# rhythkey_V1.net
KiCad netlist of a schematic drawn in EasyEDA Pro
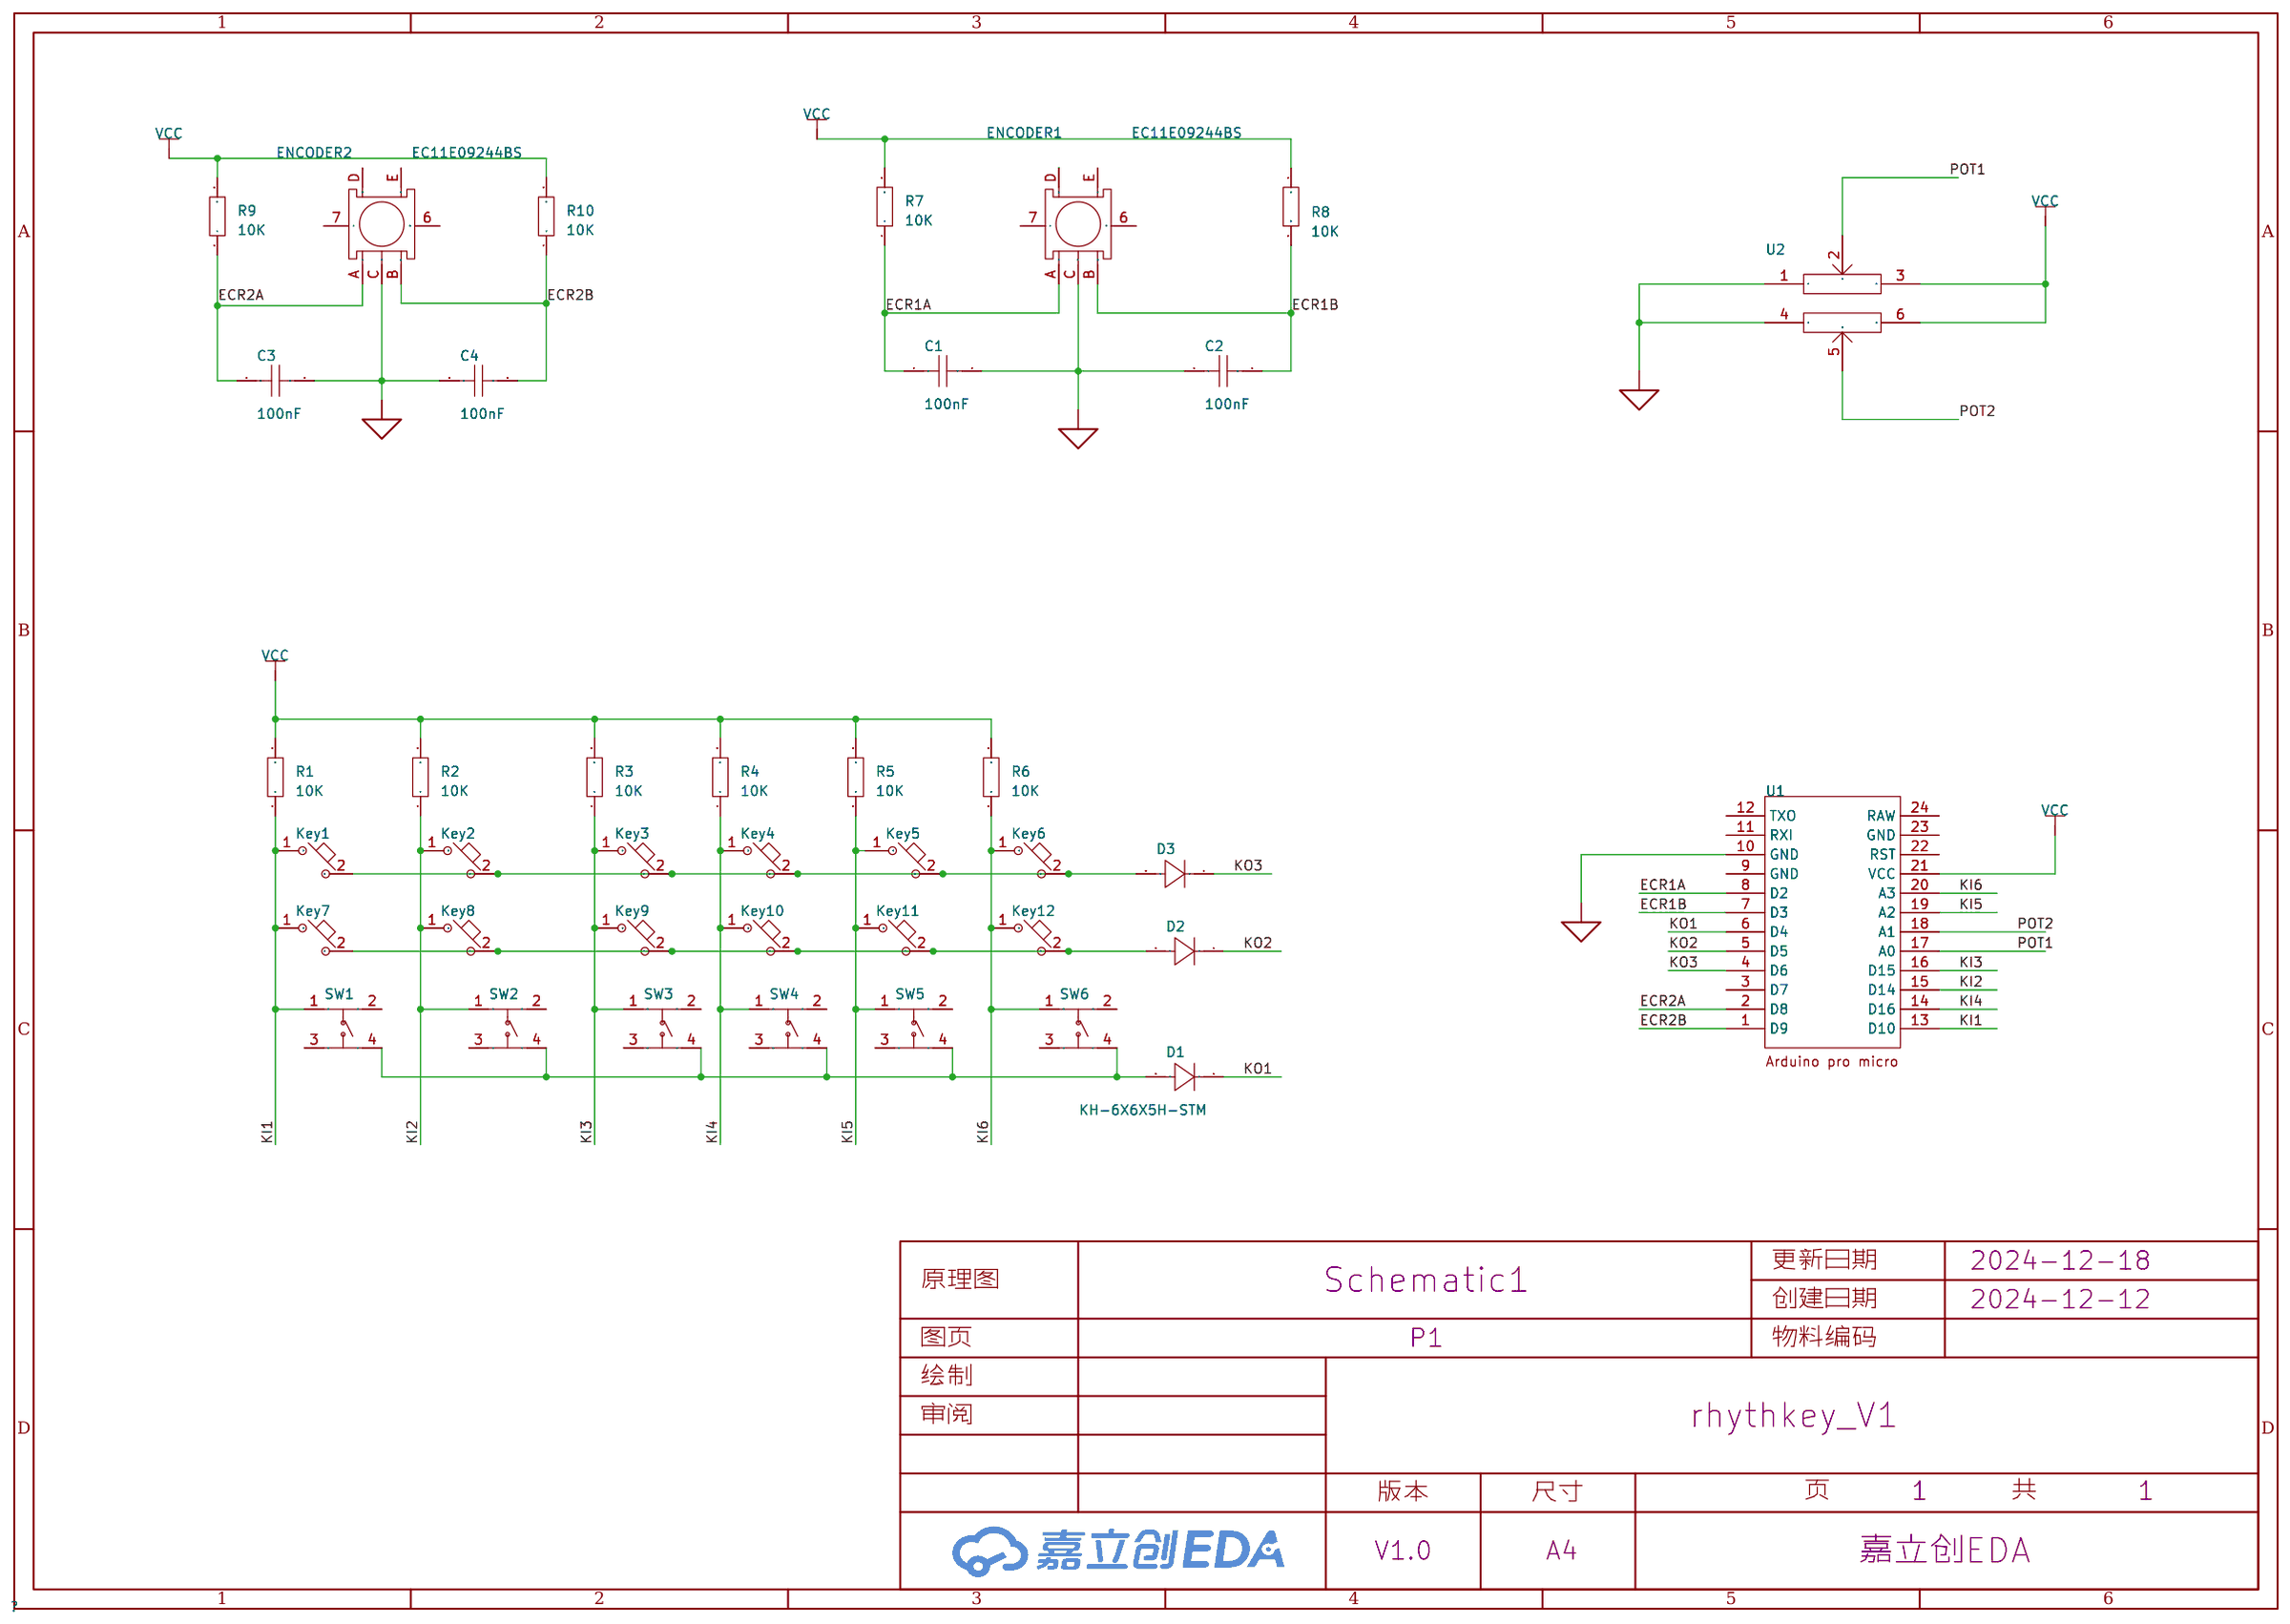
[diagram p0: schematic sheet]

(export (version "E")
  (design (tool "Eeschema 10.0.6"))
  (components
    (comp (ref "C1")
      (value "100nF")
      (footprint "easyedapro:C0805")
      (libsource (lib "easyedapro") (part "CapAcitance"))
    )
    (comp (ref "C2")
      (value "100nF")
      (footprint "easyedapro:C0805")
      (libsource (lib "easyedapro") (part "CapAcitance"))
    )
    (comp (ref "C3")
      (value "100nF")
      (footprint "easyedapro:C0805")
      (libsource (lib "easyedapro") (part "CapAcitance"))
    )
    (comp (ref "C4")
      (value "100nF")
      (footprint "easyedapro:C0805")
      (libsource (lib "easyedapro") (part "CapAcitance"))
    )
    (comp (ref "D1")
      (value "~")
      (footprint "easyedapro:SMA_1N4007")
      (libsource (lib "easyedapro") (part "D_1N4007"))
    )
    (comp (ref "D2")
      (value "~")
      (footprint "easyedapro:SMA_1N4007")
      (libsource (lib "easyedapro") (part "D_1N4007"))
    )
    (comp (ref "D3")
      (value "~")
      (footprint "easyedapro:SMA_1N4007")
      (libsource (lib "easyedapro") (part "D_1N4007"))
    )
    (comp (ref "ENCODER1")
      (value "EC11E09244BS")
      (footprint "easyedapro:SW-TH_EC11XXXXXXXX")
      (fields (field (name "Manufacturer") "ALPSALPINE(阿尔卑斯阿尔派)"))
      (libsource (lib "easyedapro") (part "EC11E09244BS"))
    )
    (comp (ref "ENCODER2")
      (value "EC11E09244BS")
      (footprint "easyedapro:SW-TH_EC11XXXXXXXX")
      (fields (field (name "Manufacturer") "ALPSALPINE(阿尔卑斯阿尔派)"))
      (libsource (lib "easyedapro") (part "EC11E09244BS"))
    )
    (comp (ref "Key1")
      (value "~")
      (footprint "easyedapro:轴座_焊接热插拔_不带灯")
      (libsource (lib "easyedapro") (part "5脚轴座"))
    )
    (comp (ref "Key2")
      (value "~")
      (footprint "easyedapro:轴座_焊接热插拔_不带灯")
      (libsource (lib "easyedapro") (part "5脚轴座"))
    )
    (comp (ref "Key3")
      (value "~")
      (footprint "easyedapro:轴座_焊接热插拔_不带灯")
      (libsource (lib "easyedapro") (part "5脚轴座"))
    )
    (comp (ref "Key4")
      (value "~")
      (footprint "easyedapro:轴座_焊接热插拔_不带灯")
      (libsource (lib "easyedapro") (part "5脚轴座"))
    )
    (comp (ref "Key5")
      (value "~")
      (footprint "easyedapro:轴座_焊接热插拔_不带灯")
      (libsource (lib "easyedapro") (part "5脚轴座"))
    )
    (comp (ref "Key6")
      (value "~")
      (footprint "easyedapro:轴座_焊接热插拔_不带灯")
      (libsource (lib "easyedapro") (part "5脚轴座"))
    )
    (comp (ref "Key7")
      (value "~")
      (footprint "easyedapro:轴座_焊接热插拔_不带灯")
      (libsource (lib "easyedapro") (part "5脚轴座"))
    )
    (comp (ref "Key8")
      (value "~")
      (footprint "easyedapro:轴座_焊接热插拔_不带灯")
      (libsource (lib "easyedapro") (part "5脚轴座"))
    )
    (comp (ref "Key9")
      (value "~")
      (footprint "easyedapro:轴座_焊接热插拔_不带灯")
      (libsource (lib "easyedapro") (part "5脚轴座"))
    )
    (comp (ref "Key10")
      (value "~")
      (footprint "easyedapro:轴座_焊接热插拔_不带灯")
      (libsource (lib "easyedapro") (part "5脚轴座"))
    )
    (comp (ref "Key11")
      (value "~")
      (footprint "easyedapro:轴座_焊接热插拔_不带灯")
      (libsource (lib "easyedapro") (part "5脚轴座"))
    )
    (comp (ref "Key12")
      (value "~")
      (footprint "easyedapro:轴座_焊接热插拔_不带灯")
      (libsource (lib "easyedapro") (part "5脚轴座"))
    )
    (comp (ref "R1") (value "10K") (footprint "easyedapro:R0805") (libsource (lib "easyedapro") (part "电阻")))
    (comp (ref "R2") (value "10K") (footprint "easyedapro:R0805") (libsource (lib "easyedapro") (part "电阻")))
    (comp (ref "R3") (value "10K") (footprint "easyedapro:R0805") (libsource (lib "easyedapro") (part "电阻")))
    (comp (ref "R4") (value "10K") (footprint "easyedapro:R0805") (libsource (lib "easyedapro") (part "电阻")))
    (comp (ref "R5") (value "10K") (footprint "easyedapro:R0805") (libsource (lib "easyedapro") (part "电阻")))
    (comp (ref "R6") (value "10K") (footprint "easyedapro:R0805") (libsource (lib "easyedapro") (part "电阻")))
    (comp (ref "R7") (value "10K") (footprint "easyedapro:R0805") (libsource (lib "easyedapro") (part "电阻")))
    (comp (ref "R8") (value "10K") (footprint "easyedapro:R0805") (libsource (lib "easyedapro") (part "电阻")))
    (comp (ref "R9") (value "10K") (footprint "easyedapro:R0805") (libsource (lib "easyedapro") (part "电阻")))
    (comp (ref "R10") (value "10K") (footprint "easyedapro:R0805") (libsource (lib "easyedapro") (part "电阻")))
    (comp (ref "SW1")
      (value "KH-6X6X5H-STM")
      (footprint "easyedapro:SW-SMD_4P-L6.0-W6.0-P4.50-LS9.0-2")
      (description "电路结构:单刀单掷;按钮形状:圆形按钮;安装方式:立贴;开关长度:6mm;开关宽度:6mm;开关高度:5mm;带支架:不带;触点电流:50mA;额定电压(DC):12V;机械寿命:8万次;")
      (fields (field (name "Manufacturer") "kinghelm(金航标)"))
      (libsource (lib "easyedapro") (part "KH-6X6X5H-STM"))
    )
    (comp (ref "SW2")
      (value "KH-6X6X5H-STM")
      (footprint "easyedapro:SW-SMD_4P-L6.0-W6.0-P4.50-LS9.0-2")
      (description "电路结构:单刀单掷;按钮形状:圆形按钮;安装方式:立贴;开关长度:6mm;开关宽度:6mm;开关高度:5mm;带支架:不带;触点电流:50mA;额定电压(DC):12V;机械寿命:8万次;")
      (fields (field (name "Manufacturer") "kinghelm(金航标)"))
      (libsource (lib "easyedapro") (part "KH-6X6X5H-STM"))
    )
    (comp (ref "SW3")
      (value "KH-6X6X5H-STM")
      (footprint "easyedapro:SW-SMD_4P-L6.0-W6.0-P4.50-LS9.0-2")
      (description "电路结构:单刀单掷;按钮形状:圆形按钮;安装方式:立贴;开关长度:6mm;开关宽度:6mm;开关高度:5mm;带支架:不带;触点电流:50mA;额定电压(DC):12V;机械寿命:8万次;")
      (fields (field (name "Manufacturer") "kinghelm(金航标)"))
      (libsource (lib "easyedapro") (part "KH-6X6X5H-STM"))
    )
    (comp (ref "SW4")
      (value "KH-6X6X5H-STM")
      (footprint "easyedapro:SW-SMD_4P-L6.0-W6.0-P4.50-LS9.0-2")
      (description "电路结构:单刀单掷;按钮形状:圆形按钮;安装方式:立贴;开关长度:6mm;开关宽度:6mm;开关高度:5mm;带支架:不带;触点电流:50mA;额定电压(DC):12V;机械寿命:8万次;")
      (fields (field (name "Manufacturer") "kinghelm(金航标)"))
      (libsource (lib "easyedapro") (part "KH-6X6X5H-STM"))
    )
    (comp (ref "SW5")
      (value "KH-6X6X5H-STM")
      (footprint "easyedapro:SW-SMD_4P-L6.0-W6.0-P4.50-LS9.0-2")
      (description "电路结构:单刀单掷;按钮形状:圆形按钮;安装方式:立贴;开关长度:6mm;开关宽度:6mm;开关高度:5mm;带支架:不带;触点电流:50mA;额定电压(DC):12V;机械寿命:8万次;")
      (fields (field (name "Manufacturer") "kinghelm(金航标)"))
      (libsource (lib "easyedapro") (part "KH-6X6X5H-STM"))
    )
    (comp (ref "SW6")
      (value "KH-6X6X5H-STM")
      (footprint "easyedapro:SW-SMD_4P-L6.0-W6.0-P4.50-LS9.0-2")
      (description "电路结构:单刀单掷;按钮形状:圆形按钮;安装方式:立贴;开关长度:6mm;开关宽度:6mm;开关高度:5mm;带支架:不带;触点电流:50mA;额定电压(DC):12V;机械寿命:8万次;")
      (fields (field (name "Manufacturer") "kinghelm(金航标)"))
      (libsource (lib "easyedapro") (part "KH-6X6X5H-STM"))
    )
    (comp (ref "U1")
      (value "~")
      (footprint "easyedapro:arduino_pro_micro")
      (libsource (lib "easyedapro") (part "arduino_pro_micro"))
    )
    (comp (ref "U2")
      (value "~")
      (footprint "easyedapro:75mm 滑台电位器")
      (libsource (lib "easyedapro") (part "75mm直滑电位器"))
    )
  )
  (nets
    (net (code "1") (name "/ECR1A") (class "Default")
      (node (ref "C1") (pin "1") (pinfunction "1_1") (pintype "input"))
      (node (ref "ENCODER1") (pin "A") (pinfunction "A_A") (pintype "unspecified"))
      (node (ref "R7") (pin "1") (pinfunction "1_1") (pintype "input"))
      (node (ref "U1") (pin "8") (pinfunction "D2_8") (pintype "input"))
    )
    (net (code "2") (name "/ECR1B") (class "Default")
      (node (ref "C2") (pin "2") (pinfunction "2_2") (pintype "input"))
      (node (ref "ENCODER1") (pin "B") (pinfunction "B_B") (pintype "unspecified"))
      (node (ref "R8") (pin "2") (pinfunction "2_2") (pintype "input"))
      (node (ref "U1") (pin "7") (pinfunction "D3_7") (pintype "input"))
    )
    (net (code "3") (name "/ECR2A") (class "Default")
      (node (ref "C3") (pin "1") (pinfunction "1_1") (pintype "input"))
      (node (ref "ENCODER2") (pin "A") (pinfunction "A_A") (pintype "unspecified"))
      (node (ref "R9") (pin "1") (pinfunction "1_1") (pintype "input"))
      (node (ref "U1") (pin "2") (pinfunction "D8_2") (pintype "input"))
    )
    (net (code "4") (name "/ECR2B") (class "Default")
      (node (ref "C4") (pin "2") (pinfunction "2_2") (pintype "input"))
      (node (ref "ENCODER2") (pin "B") (pinfunction "B_B") (pintype "unspecified"))
      (node (ref "R10") (pin "1") (pinfunction "1_1") (pintype "input"))
      (node (ref "U1") (pin "1") (pinfunction "D9_1") (pintype "input"))
    )
    (net (code "5") (name "/KI1") (class "Default")
      (node (ref "Key1") (pin "1") (pinfunction "2_1") (pintype "input"))
      (node (ref "Key7") (pin "1") (pinfunction "2_1") (pintype "input"))
      (node (ref "R1") (pin "1") (pinfunction "1_1") (pintype "input"))
      (node (ref "SW1") (pin "1") (pinfunction "1_1") (pintype "unspecified"))
      (node (ref "U1") (pin "13") (pinfunction "D10_13") (pintype "input"))
    )
    (net (code "6") (name "/KI2") (class "Default")
      (node (ref "Key2") (pin "1") (pinfunction "2_1") (pintype "input"))
      (node (ref "Key8") (pin "1") (pinfunction "2_1") (pintype "input"))
      (node (ref "R2") (pin "1") (pinfunction "1_1") (pintype "input"))
      (node (ref "SW2") (pin "1") (pinfunction "1_1") (pintype "unspecified"))
      (node (ref "U1") (pin "15") (pinfunction "D14_15") (pintype "input"))
    )
    (net (code "7") (name "/KI3") (class "Default")
      (node (ref "Key3") (pin "1") (pinfunction "2_1") (pintype "input"))
      (node (ref "Key9") (pin "1") (pinfunction "2_1") (pintype "input"))
      (node (ref "R3") (pin "1") (pinfunction "1_1") (pintype "input"))
      (node (ref "SW3") (pin "1") (pinfunction "1_1") (pintype "unspecified"))
      (node (ref "U1") (pin "16") (pinfunction "D15_16") (pintype "input"))
    )
    (net (code "8") (name "/KI4") (class "Default")
      (node (ref "Key10") (pin "1") (pinfunction "2_1") (pintype "input"))
      (node (ref "Key4") (pin "1") (pinfunction "2_1") (pintype "input"))
      (node (ref "R4") (pin "1") (pinfunction "1_1") (pintype "input"))
      (node (ref "SW4") (pin "1") (pinfunction "1_1") (pintype "unspecified"))
      (node (ref "U1") (pin "14") (pinfunction "D16_14") (pintype "input"))
    )
    (net (code "9") (name "/KI5") (class "Default")
      (node (ref "Key11") (pin "1") (pinfunction "2_1") (pintype "input"))
      (node (ref "Key5") (pin "1") (pinfunction "2_1") (pintype "input"))
      (node (ref "R5") (pin "1") (pinfunction "1_1") (pintype "input"))
      (node (ref "SW5") (pin "1") (pinfunction "1_1") (pintype "unspecified"))
      (node (ref "U1") (pin "19") (pinfunction "A2_19") (pintype "input"))
    )
    (net (code "10") (name "/KI6") (class "Default")
      (node (ref "Key12") (pin "1") (pinfunction "2_1") (pintype "input"))
      (node (ref "Key6") (pin "1") (pinfunction "2_1") (pintype "input"))
      (node (ref "R6") (pin "1") (pinfunction "1_1") (pintype "input"))
      (node (ref "SW6") (pin "1") (pinfunction "1_1") (pintype "unspecified"))
      (node (ref "U1") (pin "20") (pinfunction "A3_20") (pintype "input"))
    )
    (net (code "11") (name "/KO1") (class "Default")
      (node (ref "D1") (pin "1") (pinfunction "K_1") (pintype "input"))
      (node (ref "U1") (pin "6") (pinfunction "D4_6") (pintype "input"))
    )
    (net (code "12") (name "/KO2") (class "Default")
      (node (ref "D2") (pin "1") (pinfunction "K_1") (pintype "input"))
      (node (ref "U1") (pin "5") (pinfunction "D5_5") (pintype "input"))
    )
    (net (code "13") (name "/KO3") (class "Default")
      (node (ref "D3") (pin "1") (pinfunction "K_1") (pintype "input"))
      (node (ref "U1") (pin "4") (pinfunction "D6_4") (pintype "input"))
    )
    (net (code "14") (name "/POT1") (class "Default")
      (node (ref "U1") (pin "17") (pinfunction "A0_17") (pintype "input"))
      (node (ref "U2") (pin "2") (pinfunction "5_2") (pintype "input"))
    )
    (net (code "15") (name "/POT2") (class "Default")
      (node (ref "U1") (pin "18") (pinfunction "A1_18") (pintype "input"))
      (node (ref "U2") (pin "5") (pinfunction "6_5") (pintype "input"))
    )
    (net (code "16") (name "AGND") (class "Default")
      (node (ref "C1") (pin "2") (pinfunction "2_2") (pintype "input"))
      (node (ref "C2") (pin "1") (pinfunction "1_1") (pintype "input"))
      (node (ref "C3") (pin "2") (pinfunction "2_2") (pintype "input"))
      (node (ref "C4") (pin "1") (pinfunction "1_1") (pintype "input"))
      (node (ref "ENCODER1") (pin "C") (pinfunction "C_C") (pintype "unspecified"))
      (node (ref "ENCODER2") (pin "C") (pinfunction "C_C") (pintype "unspecified"))
      (node (ref "U1") (pin "10") (pinfunction "GND_10") (pintype "input"))
      (node (ref "U2") (pin "1") (pinfunction "1_1") (pintype "input"))
      (node (ref "U2") (pin "4") (pinfunction "4_4") (pintype "input"))
    )
    (net (code "17") (name "Net-(D1-A)") (class "Default")
      (node (ref "D1") (pin "2") (pinfunction "A_2") (pintype "input"))
      (node (ref "SW1") (pin "4") (pinfunction "4_4") (pintype "unspecified"))
      (node (ref "SW2") (pin "4") (pinfunction "4_4") (pintype "unspecified"))
      (node (ref "SW3") (pin "4") (pinfunction "4_4") (pintype "unspecified"))
      (node (ref "SW4") (pin "4") (pinfunction "4_4") (pintype "unspecified"))
      (node (ref "SW5") (pin "4") (pinfunction "4_4") (pintype "unspecified"))
      (node (ref "SW6") (pin "4") (pinfunction "4_4") (pintype "unspecified"))
    )
    (net (code "18") (name "Net-(D2-A)") (class "Default")
      (node (ref "D2") (pin "2") (pinfunction "A_2") (pintype "input"))
      (node (ref "Key10") (pin "2") (pinfunction "1_2") (pintype "input"))
      (node (ref "Key11") (pin "2") (pinfunction "1_2") (pintype "input"))
      (node (ref "Key12") (pin "2") (pinfunction "1_2") (pintype "input"))
      (node (ref "Key7") (pin "2") (pinfunction "1_2") (pintype "input"))
      (node (ref "Key8") (pin "2") (pinfunction "1_2") (pintype "input"))
      (node (ref "Key9") (pin "2") (pinfunction "1_2") (pintype "input"))
    )
    (net (code "19") (name "Net-(D3-A)") (class "Default")
      (node (ref "D3") (pin "2") (pinfunction "A_2") (pintype "input"))
      (node (ref "Key1") (pin "2") (pinfunction "1_2") (pintype "input"))
      (node (ref "Key2") (pin "2") (pinfunction "1_2") (pintype "input"))
      (node (ref "Key3") (pin "2") (pinfunction "1_2") (pintype "input"))
      (node (ref "Key4") (pin "2") (pinfunction "1_2") (pintype "input"))
      (node (ref "Key5") (pin "2") (pinfunction "1_2") (pintype "input"))
      (node (ref "Key6") (pin "2") (pinfunction "1_2") (pintype "input"))
    )
    (net (code "20") (name "VCC") (class "Default")
      (node (ref "R1") (pin "2") (pinfunction "2_2") (pintype "input"))
      (node (ref "R10") (pin "2") (pinfunction "2_2") (pintype "input"))
      (node (ref "R2") (pin "2") (pinfunction "2_2") (pintype "input"))
      (node (ref "R3") (pin "2") (pinfunction "2_2") (pintype "input"))
      (node (ref "R4") (pin "2") (pinfunction "2_2") (pintype "input"))
      (node (ref "R5") (pin "2") (pinfunction "2_2") (pintype "input"))
      (node (ref "R6") (pin "2") (pinfunction "2_2") (pintype "input"))
      (node (ref "R7") (pin "2") (pinfunction "2_2") (pintype "input"))
      (node (ref "R8") (pin "1") (pinfunction "1_1") (pintype "input"))
      (node (ref "R9") (pin "2") (pinfunction "2_2") (pintype "input"))
      (node (ref "U1") (pin "21") (pinfunction "VCC_21") (pintype "input"))
      (node (ref "U2") (pin "3") (pinfunction "2_3") (pintype "input"))
      (node (ref "U2") (pin "6") (pinfunction "3_6") (pintype "input"))
    )
    (net (code "21") (name "unconnected-(ENCODER1-Pad6)") (class "Default")
      (node (ref "ENCODER1") (pin "6") (pinfunction "6_6") (pintype "unspecified"))
    )
    (net (code "22") (name "unconnected-(ENCODER1-Pad7)") (class "Default")
      (node (ref "ENCODER1") (pin "7") (pinfunction "7_7") (pintype "unspecified"))
    )
    (net (code "23") (name "unconnected-(ENCODER1-PadD)") (class "Default")
      (node (ref "ENCODER1") (pin "D") (pinfunction "D_D") (pintype "unspecified"))
    )
    (net (code "24") (name "unconnected-(ENCODER1-PadE)") (class "Default")
      (node (ref "ENCODER1") (pin "E") (pinfunction "E_E") (pintype "unspecified"))
    )
    (net (code "25") (name "unconnected-(ENCODER2-Pad6)") (class "Default")
      (node (ref "ENCODER2") (pin "6") (pinfunction "6_6") (pintype "unspecified"))
    )
    (net (code "26") (name "unconnected-(ENCODER2-Pad7)") (class "Default")
      (node (ref "ENCODER2") (pin "7") (pinfunction "7_7") (pintype "unspecified"))
    )
    (net (code "27") (name "unconnected-(ENCODER2-PadD)") (class "Default")
      (node (ref "ENCODER2") (pin "D") (pinfunction "D_D") (pintype "unspecified"))
    )
    (net (code "28") (name "unconnected-(ENCODER2-PadE)") (class "Default")
      (node (ref "ENCODER2") (pin "E") (pinfunction "E_E") (pintype "unspecified"))
    )
    (net (code "29") (name "unconnected-(SW1-Pad2)") (class "Default")
      (node (ref "SW1") (pin "2") (pinfunction "2_2") (pintype "unspecified"))
    )
    (net (code "30") (name "unconnected-(SW1-Pad3)") (class "Default")
      (node (ref "SW1") (pin "3") (pinfunction "3_3") (pintype "unspecified"))
    )
    (net (code "31") (name "unconnected-(SW2-Pad2)") (class "Default")
      (node (ref "SW2") (pin "2") (pinfunction "2_2") (pintype "unspecified"))
    )
    (net (code "32") (name "unconnected-(SW2-Pad3)") (class "Default")
      (node (ref "SW2") (pin "3") (pinfunction "3_3") (pintype "unspecified"))
    )
    (net (code "33") (name "unconnected-(SW3-Pad2)") (class "Default")
      (node (ref "SW3") (pin "2") (pinfunction "2_2") (pintype "unspecified"))
    )
    (net (code "34") (name "unconnected-(SW3-Pad3)") (class "Default")
      (node (ref "SW3") (pin "3") (pinfunction "3_3") (pintype "unspecified"))
    )
    (net (code "35") (name "unconnected-(SW4-Pad2)") (class "Default")
      (node (ref "SW4") (pin "2") (pinfunction "2_2") (pintype "unspecified"))
    )
    (net (code "36") (name "unconnected-(SW4-Pad3)") (class "Default")
      (node (ref "SW4") (pin "3") (pinfunction "3_3") (pintype "unspecified"))
    )
    (net (code "37") (name "unconnected-(SW5-Pad2)") (class "Default")
      (node (ref "SW5") (pin "2") (pinfunction "2_2") (pintype "unspecified"))
    )
    (net (code "38") (name "unconnected-(SW5-Pad3)") (class "Default")
      (node (ref "SW5") (pin "3") (pinfunction "3_3") (pintype "unspecified"))
    )
    (net (code "39") (name "unconnected-(SW6-Pad2)") (class "Default")
      (node (ref "SW6") (pin "2") (pinfunction "2_2") (pintype "unspecified"))
    )
    (net (code "40") (name "unconnected-(SW6-Pad3)") (class "Default")
      (node (ref "SW6") (pin "3") (pinfunction "3_3") (pintype "unspecified"))
    )
    (net (code "41") (name "unconnected-(U1-D7-Pad3)") (class "Default")
      (node (ref "U1") (pin "3") (pinfunction "D7_3") (pintype "input"))
    )
    (net (code "42") (name "unconnected-(U1-GND-Pad9)") (class "Default")
      (node (ref "U1") (pin "9") (pinfunction "GND_9") (pintype "input"))
    )
    (net (code "43") (name "unconnected-(U1-GND-Pad23)") (class "Default")
      (node (ref "U1") (pin "23") (pinfunction "GND_23") (pintype "input"))
    )
    (net (code "44") (name "unconnected-(U1-RAW-Pad24)") (class "Default")
      (node (ref "U1") (pin "24") (pinfunction "RAW_24") (pintype "input"))
    )
    (net (code "45") (name "unconnected-(U1-RST-Pad22)") (class "Default")
      (node (ref "U1") (pin "22") (pinfunction "RST_22") (pintype "input"))
    )
    (net (code "46") (name "unconnected-(U1-RXI-Pad11)") (class "Default")
      (node (ref "U1") (pin "11") (pinfunction "RXI_11") (pintype "input"))
    )
    (net (code "47") (name "unconnected-(U1-TXO-Pad12)") (class "Default")
      (node (ref "U1") (pin "12") (pinfunction "TXO_12") (pintype "input"))
    )
  )
)
